# Interface_Current_Sensor_1.net
KiCad netlist of a schematic drawn in Altium Designer
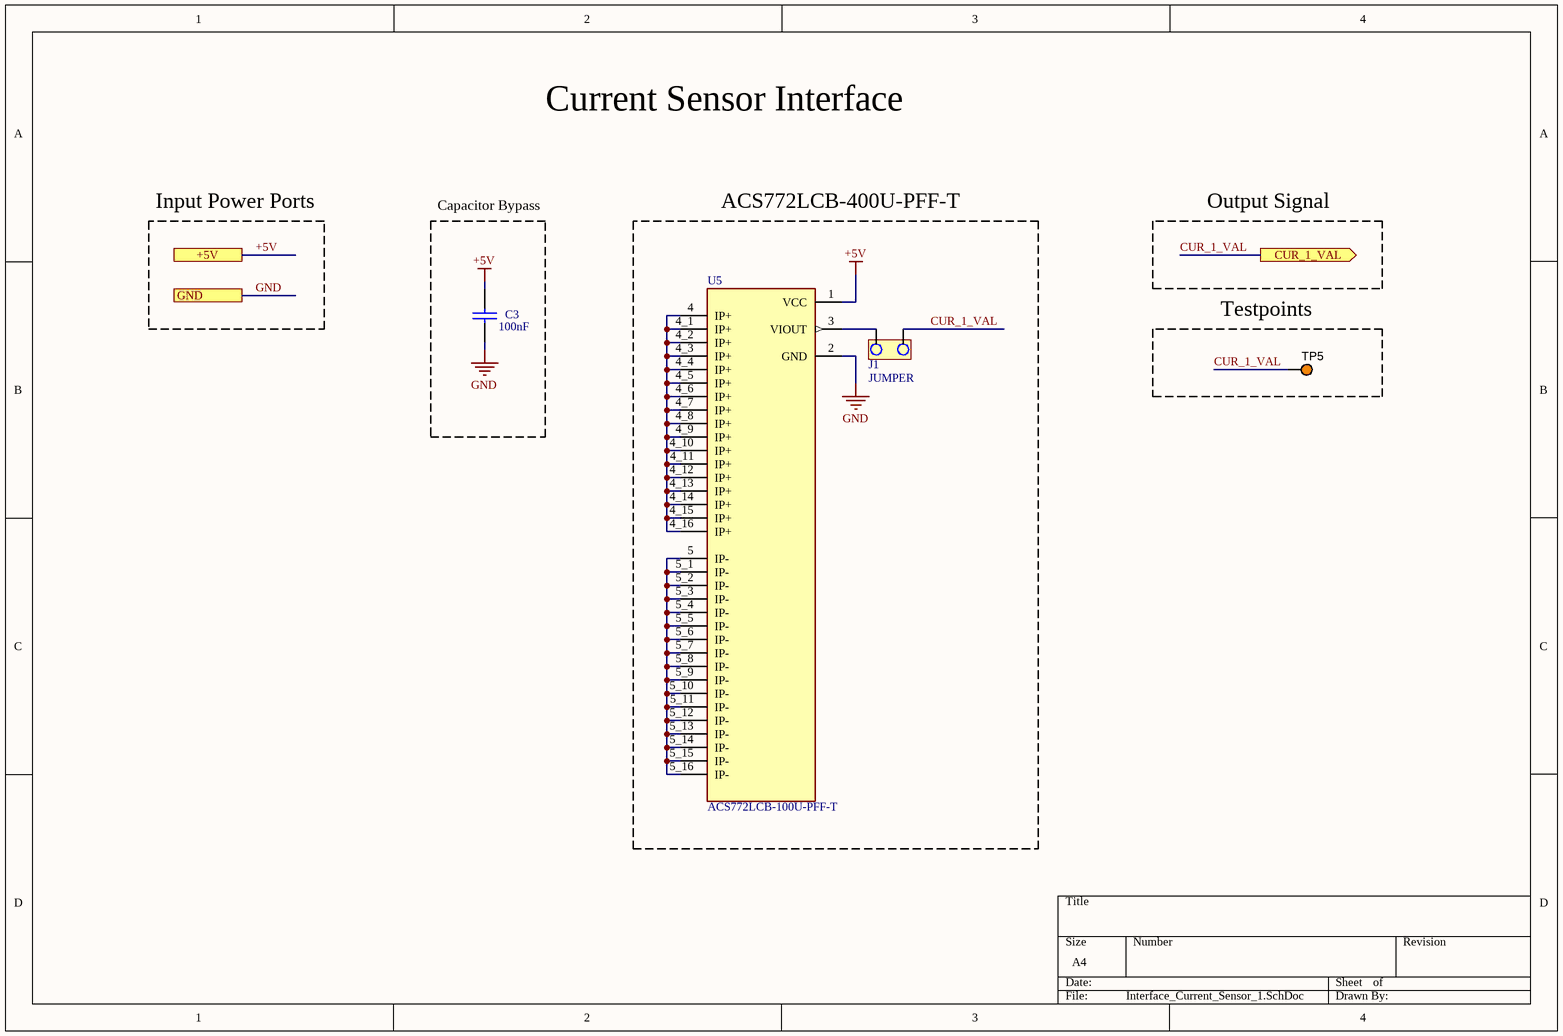
[diagram p0: Interface_Current_Sensor_1.SchDoc]

(export (version "E")
  (design (tool "Eeschema 10.0.6"))
  (components
    (comp (ref "C3") (value "100nF") (footprint "CAP200") (libsource (lib "LIBEBAL") (part "CAP")))
    (comp (ref "J1") (value "JUMPER") (footprint "JUMPER2") (libsource (lib "LIBEBAL") (part "JUMPER")))
    (comp (ref "TP5")
      (value "5003")
      (footprint "KSTN-5003")
      (description "Test Point, Orange, Height 4.6 mm, Tail Length 3 mm, 1-Pin THD, RoHS")
      (fields (field (name "MANUFACTURER") "Keystone"))
      (libsource (lib "TD") (part "TESTPOINT_ORANGE"))
    )
    (comp (ref "U5")
      (value "ACS772LCB-100U-PFF-T")
      (footprint "XDCR_ACS772LCB-100U-PFF-T")
      (description "Current Sensor 100A 1 Channel Hall Effect Unidirectional 5-CB Formed Leads, PFF")
      (fields (field (name "MF") "Allegro MicroSystems LLC"))
      (libsource (lib "TD") (part "ACS772LCB-100U-PFF-T"))
    )
  )
  (nets
    (net (code "1") (name "+5V") (class "Default")
      (node (ref "C3") (pin "1") (pinfunction "1_1") (pintype "passive"))
      (node (ref "U5") (pin "1") (pinfunction "VCC_1") (pintype "power_in"))
    )
    (net (code "2") (name "/CUR_1_VAL") (class "Default")
      (node (ref "J1") (pin "2") (pinfunction "2_2") (pintype "passive"))
      (node (ref "TP5") (pin "1") (pinfunction "1_1") (pintype "passive"))
    )
    (net (code "3") (name "GND") (class "Default")
      (node (ref "C3") (pin "2") (pinfunction "2_2") (pintype "passive"))
      (node (ref "U5") (pin "2") (pinfunction "GND_2") (pintype "power_in"))
    )
    (net (code "4") (name "Net-(U5-IP+-Pad4)") (class "Default")
      (node (ref "U5") (pin "4") (pinfunction "IP+_4") (pintype "passive"))
      (node (ref "U5") (pin "4_1") (pinfunction "IP+_4_1") (pintype "passive"))
      (node (ref "U5") (pin "4_10") (pinfunction "IP+_4_10") (pintype "passive"))
      (node (ref "U5") (pin "4_11") (pinfunction "IP+_4_11") (pintype "passive"))
      (node (ref "U5") (pin "4_12") (pinfunction "IP+_4_12") (pintype "passive"))
      (node (ref "U5") (pin "4_13") (pinfunction "IP+_4_13") (pintype "passive"))
      (node (ref "U5") (pin "4_14") (pinfunction "IP+_4_14") (pintype "passive"))
      (node (ref "U5") (pin "4_15") (pinfunction "IP+_4_15") (pintype "passive"))
      (node (ref "U5") (pin "4_16") (pinfunction "IP+_4_16") (pintype "passive"))
      (node (ref "U5") (pin "4_2") (pinfunction "IP+_4_2") (pintype "passive"))
      (node (ref "U5") (pin "4_3") (pinfunction "IP+_4_3") (pintype "passive"))
      (node (ref "U5") (pin "4_4") (pinfunction "IP+_4_4") (pintype "passive"))
      (node (ref "U5") (pin "4_5") (pinfunction "IP+_4_5") (pintype "passive"))
      (node (ref "U5") (pin "4_6") (pinfunction "IP+_4_6") (pintype "passive"))
      (node (ref "U5") (pin "4_7") (pinfunction "IP+_4_7") (pintype "passive"))
      (node (ref "U5") (pin "4_8") (pinfunction "IP+_4_8") (pintype "passive"))
      (node (ref "U5") (pin "4_9") (pinfunction "IP+_4_9") (pintype "passive"))
    )
    (net (code "5") (name "Net-(U5-IP--Pad5)") (class "Default")
      (node (ref "U5") (pin "5") (pinfunction "IP-_5") (pintype "passive"))
      (node (ref "U5") (pin "5_1") (pinfunction "IP-_5_1") (pintype "passive"))
      (node (ref "U5") (pin "5_10") (pinfunction "IP-_5_10") (pintype "passive"))
      (node (ref "U5") (pin "5_11") (pinfunction "IP-_5_11") (pintype "passive"))
      (node (ref "U5") (pin "5_12") (pinfunction "IP-_5_12") (pintype "passive"))
      (node (ref "U5") (pin "5_13") (pinfunction "IP-_5_13") (pintype "passive"))
      (node (ref "U5") (pin "5_14") (pinfunction "IP-_5_14") (pintype "passive"))
      (node (ref "U5") (pin "5_15") (pinfunction "IP-_5_15") (pintype "passive"))
      (node (ref "U5") (pin "5_16") (pinfunction "IP-_5_16") (pintype "passive"))
      (node (ref "U5") (pin "5_2") (pinfunction "IP-_5_2") (pintype "passive"))
      (node (ref "U5") (pin "5_3") (pinfunction "IP-_5_3") (pintype "passive"))
      (node (ref "U5") (pin "5_4") (pinfunction "IP-_5_4") (pintype "passive"))
      (node (ref "U5") (pin "5_5") (pinfunction "IP-_5_5") (pintype "passive"))
      (node (ref "U5") (pin "5_6") (pinfunction "IP-_5_6") (pintype "passive"))
      (node (ref "U5") (pin "5_7") (pinfunction "IP-_5_7") (pintype "passive"))
      (node (ref "U5") (pin "5_8") (pinfunction "IP-_5_8") (pintype "passive"))
      (node (ref "U5") (pin "5_9") (pinfunction "IP-_5_9") (pintype "passive"))
    )
    (net (code "6") (name "Net-(U5-VIOUT)") (class "Default")
      (node (ref "J1") (pin "1") (pinfunction "1_1") (pintype "passive"))
      (node (ref "U5") (pin "3") (pinfunction "VIOUT_3") (pintype "output"))
    )
  )
)
